# SI7051.net
KiCad netlist of a schematic drawn in EAGLE
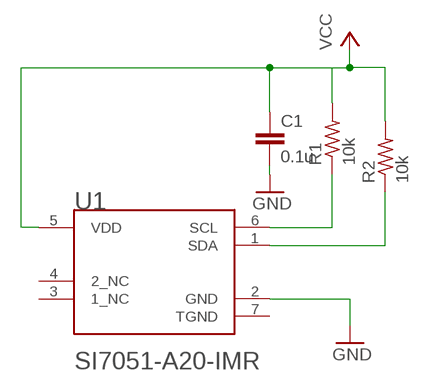
[diagram p0: schematic, sheet 1]

(export (version "E")
  (design (tool "Eeschema 10.0.6"))
  (components
    (comp (ref "C1")
      (value "0.1u")
      (footprint "eagle-import:C0603")
      (libsource (lib "eagle-import") (part "C-EUC0603"))
    )
    (comp (ref "R1")
      (value "10k")
      (footprint "eagle-import:R0603")
      (libsource (lib "eagle-import") (part "R-US_R0603"))
    )
    (comp (ref "R2")
      (value "10k")
      (footprint "eagle-import:R0603")
      (libsource (lib "eagle-import") (part "R-US_R0603"))
    )
    (comp (ref "U1")
      (value "SILICON_LABS_SI7051-A20-IMRSILICON_LABS_SI7051-A20-IMR_0_3")
      (footprint "eagle-import:SILICON_LABS_SI7051-A20-IMR_3")
      (fields
        (field (name "DIGIKEY_PART_NUMBER") "336-4764-1-ND")
        (field (name "MF") "Silicon Labs")
        (field (name "MOUSER_PART_NUMBER") "634-SI7051-A20-IMR")
      )
      (libsource (lib "eagle-import") (part "SILICON_LABS_SI7051-A20-IMRSILICON_LABS_SI7051-A20-IMR_0_3"))
    )
  )
  (nets
    (net (code "1") (name "/TGND") (class "Default")
      (node (ref "U1") (pin "7") (pinfunction "TGND_7") (pintype "power_in"))
    )
    (net (code "2") (name "GND") (class "Default")
      (node (ref "C1") (pin "2") (pinfunction "2_2") (pintype "passive"))
      (node (ref "U1") (pin "2") (pinfunction "GND_2") (pintype "power_in"))
    )
    (net (code "3") (name "Net-(U1-SCL)") (class "Default")
      (node (ref "R1") (pin "1") (pinfunction "1_1") (pintype "passive"))
      (node (ref "U1") (pin "6") (pinfunction "SCL_6") (pintype "input"))
    )
    (net (code "4") (name "Net-(U1-SDA)") (class "Default")
      (node (ref "R2") (pin "1") (pinfunction "1_1") (pintype "passive"))
      (node (ref "U1") (pin "1") (pinfunction "SDA_1") (pintype "bidirectional"))
    )
    (net (code "5") (name "VCC") (class "Default")
      (node (ref "C1") (pin "1") (pinfunction "1_1") (pintype "passive"))
      (node (ref "R1") (pin "2") (pinfunction "2_2") (pintype "passive"))
      (node (ref "R2") (pin "2") (pinfunction "2_2") (pintype "passive"))
      (node (ref "U1") (pin "5") (pinfunction "VDD_5") (pintype "power_in"))
    )
    (net (code "6") (name "unconnected-(U1-1_NC-Pad3)") (class "Default")
      (node (ref "U1") (pin "3") (pinfunction "1_NC_3") (pintype "passive"))
    )
    (net (code "7") (name "unconnected-(U1-2_NC-Pad4)") (class "Default")
      (node (ref "U1") (pin "4") (pinfunction "2_NC_4") (pintype "passive"))
    )
  )
)
